# Interface.net
KiCad netlist of a schematic drawn in Altium Designer
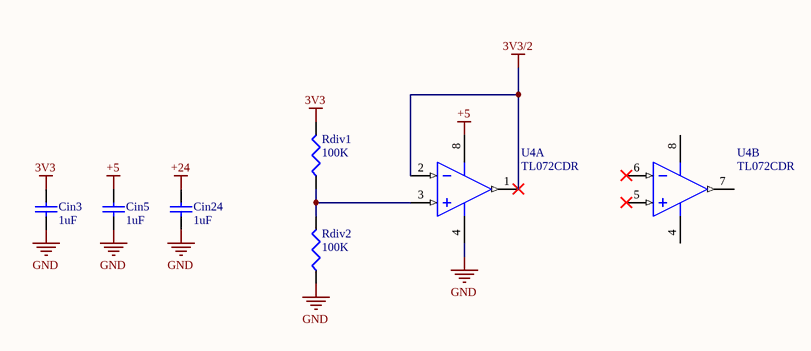
[diagram p0: Interface.SchDoc]

(export (version "E")
  (design (tool "Eeschema 10.0.6"))
  (components
    (comp (ref "Cin3")
      (value "1uF")
      (footprint "C0805")
      (description "Capacitor")
      (fields (field (name "PUBLISHER") "Altium Limited"))
      (libsource (lib "Miscellaneous Devices") (part "Cap"))
    )
    (comp (ref "Cin5")
      (value "1uF")
      (footprint "C0805")
      (description "Capacitor")
      (fields (field (name "PUBLISHER") "Altium Limited"))
      (libsource (lib "Miscellaneous Devices") (part "Cap"))
    )
    (comp (ref "Cin24")
      (value "1uF")
      (footprint "C0805")
      (description "Capacitor")
      (fields (field (name "PUBLISHER") "Altium Limited"))
      (libsource (lib "Miscellaneous Devices") (part "Cap"))
    )
    (comp (ref "Rdiv1")
      (value "100K")
      (footprint "J1-0603")
      (description "Resistor")
      (fields (field (name "PUBLISHER") "Altium Limited"))
      (libsource (lib "Miscellaneous Devices") (part "Res3"))
    )
    (comp (ref "Rdiv2")
      (value "100K")
      (footprint "J1-0603")
      (description "Resistor")
      (fields (field (name "PUBLISHER") "Altium Limited"))
      (libsource (lib "Miscellaneous Devices") (part "Res3"))
    )
    (comp (ref "U4")
      (value "TL072CDR")
      (footprint "D0008A_M")
      (fields (field (name "MANUFACTURER") "Texas Instruments"))
      (libsource (lib "Altium Content Vault") (part "TI-AMP-D6-2-8_D"))
    )
  )
  (nets
    (net (code "1") (name "+5") (class "Default")
      (node (ref "Cin5") (pin "2") (pinfunction "2_2") (pintype "passive"))
      (node (ref "U4") (pin "8") (pinfunction "VCC+_8") (pintype "power_in"))
    )
    (net (code "2") (name "+24") (class "Default")
      (node (ref "Cin24") (pin "2") (pinfunction "2_2") (pintype "passive"))
    )
    (net (code "3") (name "3V3") (class "Default")
      (node (ref "Cin3") (pin "2") (pinfunction "2_2") (pintype "passive"))
      (node (ref "Rdiv1") (pin "2") (pinfunction "2_2") (pintype "passive"))
    )
    (net (code "4") (name "3V3{slash}2") (class "Default")
      (node (ref "U4") (pin "1") (pinfunction "OUT1_1") (pintype "output"))
      (node (ref "U4") (pin "2") (pinfunction "IN1-_2") (pintype "input"))
    )
    (net (code "5") (name "GND") (class "Default")
      (node (ref "Cin24") (pin "1") (pinfunction "1_1") (pintype "passive"))
      (node (ref "Cin3") (pin "1") (pinfunction "1_1") (pintype "passive"))
      (node (ref "Cin5") (pin "1") (pinfunction "1_1") (pintype "passive"))
      (node (ref "Rdiv2") (pin "1") (pinfunction "1_1") (pintype "passive"))
      (node (ref "U4") (pin "4") (pinfunction "VCC-_4") (pintype "power_in"))
    )
    (net (code "6") (name "Net-(U4A-IN1+)") (class "Default")
      (node (ref "Rdiv1") (pin "1") (pinfunction "1_1") (pintype "passive"))
      (node (ref "Rdiv2") (pin "2") (pinfunction "2_2") (pintype "passive"))
      (node (ref "U4") (pin "3") (pinfunction "IN1+_3") (pintype "input"))
    )
    (net (code "7") (name "unconnected-(U4B-IN2+-Pad5)") (class "Default")
      (node (ref "U4") (pin "5") (pinfunction "IN2+_5") (pintype "input+no_connect"))
    )
    (net (code "8") (name "unconnected-(U4B-IN2--Pad6)") (class "Default")
      (node (ref "U4") (pin "6") (pinfunction "IN2-_6") (pintype "input+no_connect"))
    )
    (net (code "9") (name "unconnected-(U4B-OUT2-Pad7)") (class "Default")
      (node (ref "U4") (pin "7") (pinfunction "OUT2_7") (pintype "output"))
    )
    (net (code "10") (name "unconnected-(U4B-VCC+-Pad8)") (class "Default")
      (node (ref "U4") (pin "8") (pinfunction "VCC+_8") (pintype "power_in"))
    )
    (net (code "11") (name "unconnected-(U4B-VCC--Pad4)") (class "Default")
      (node (ref "U4") (pin "4") (pinfunction "VCC-_4") (pintype "power_in"))
    )
  )
)
